# TopLevel.net
KiCad netlist of a schematic drawn in Altium Designer
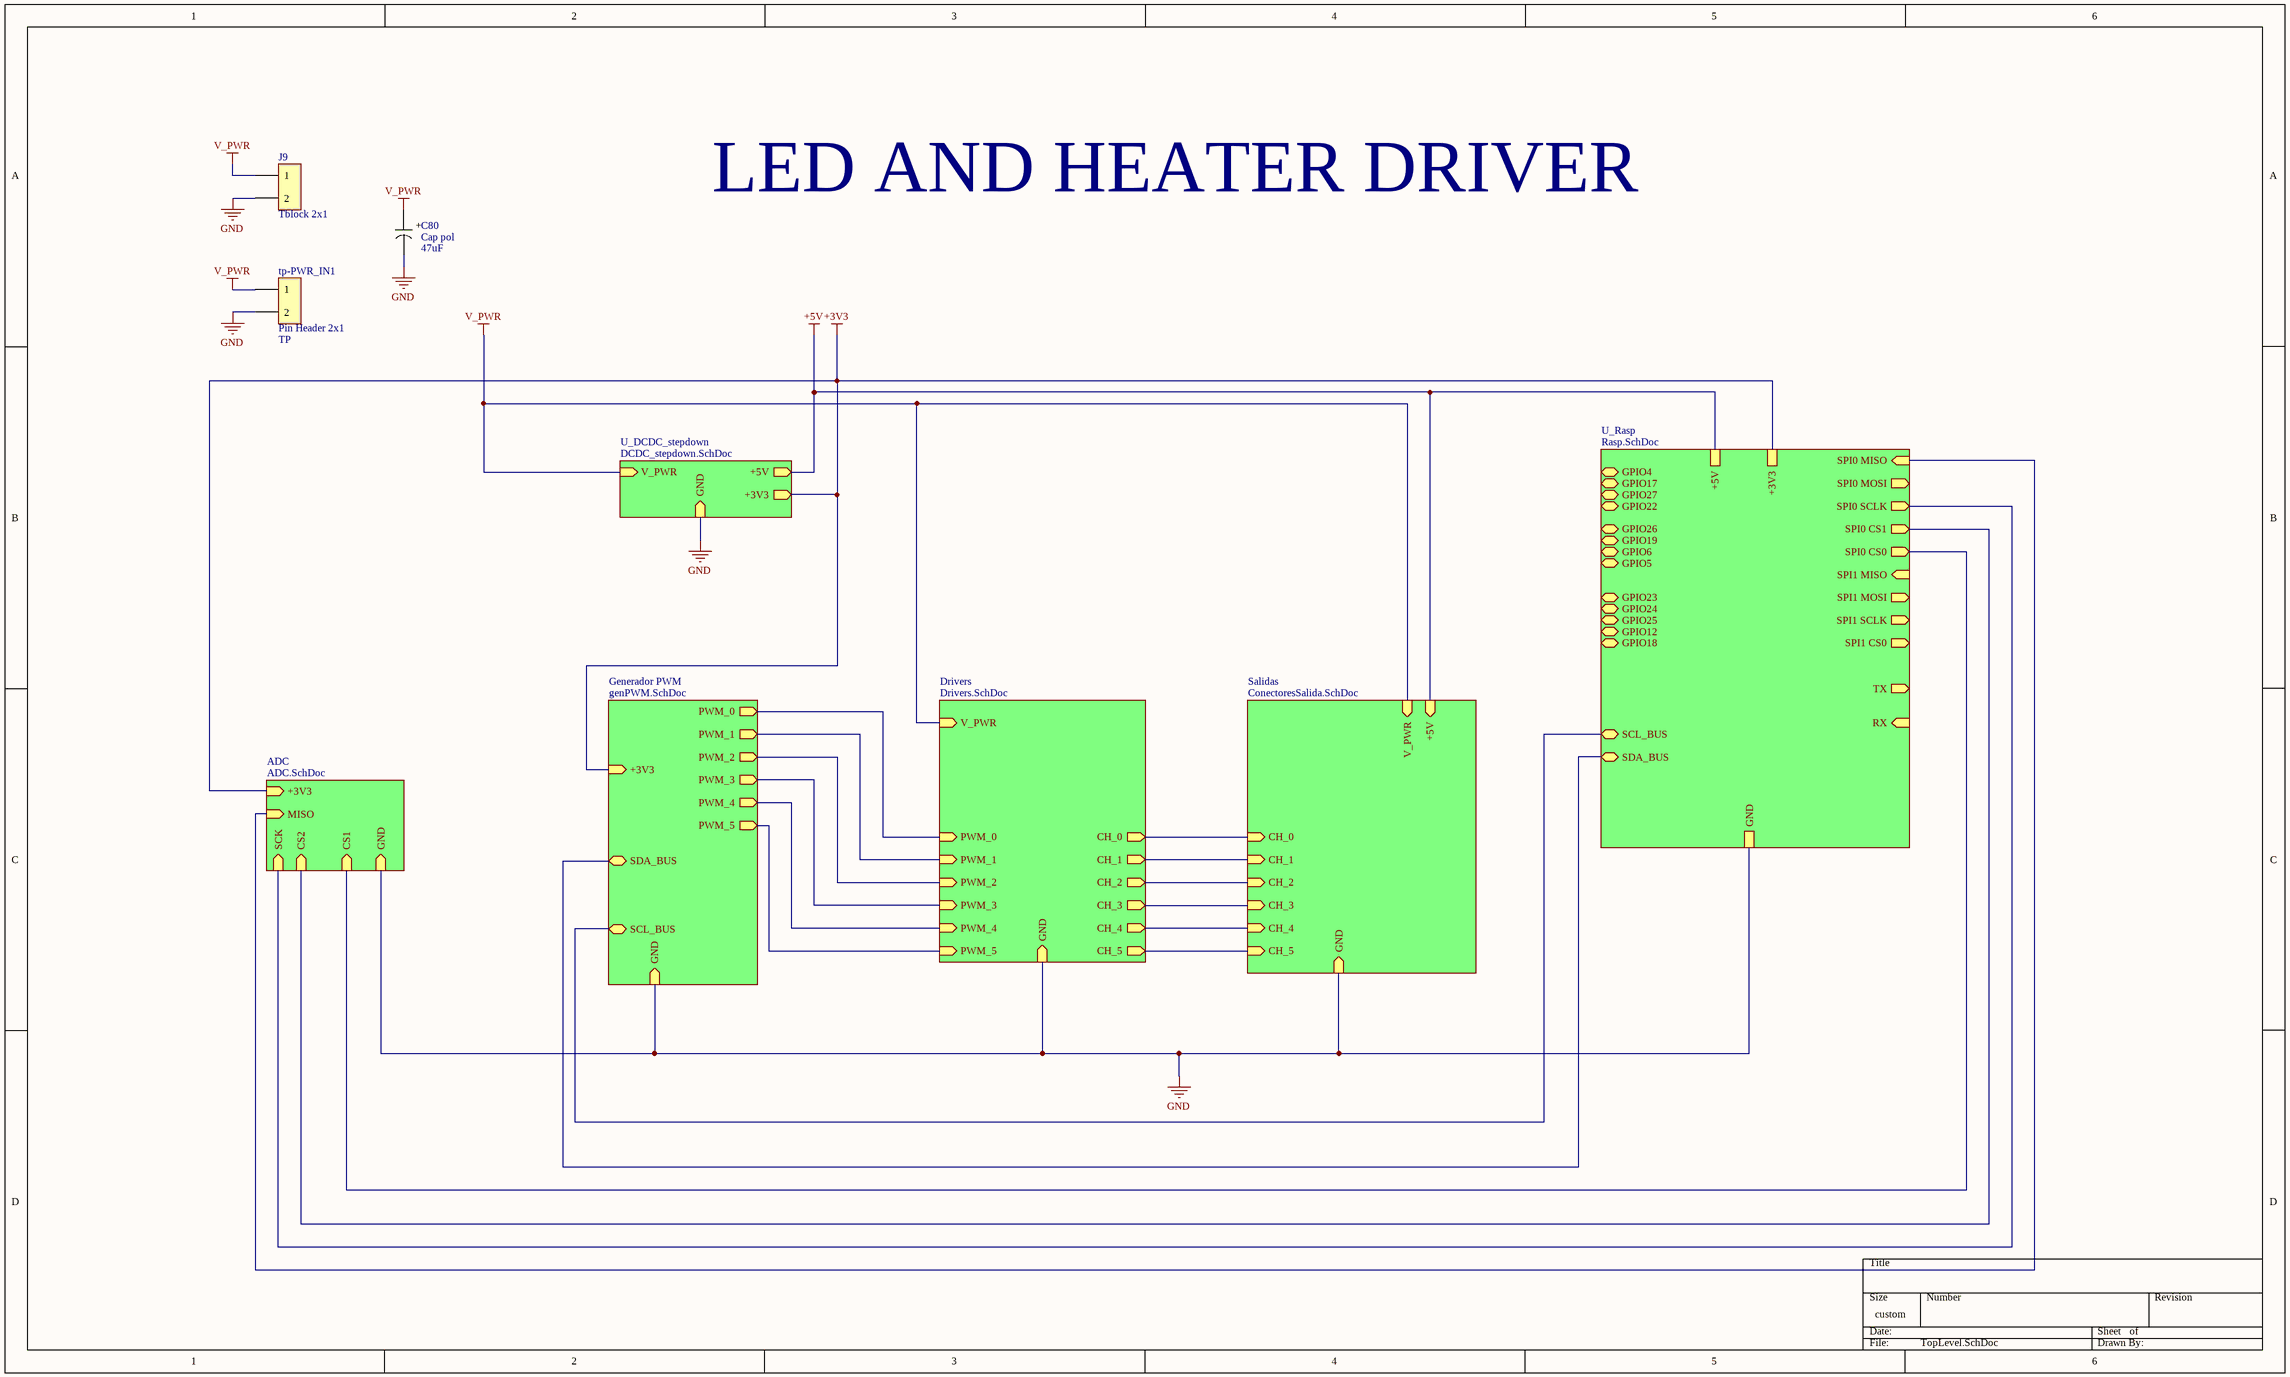
[diagram p0: TopLevel.SchDoc]

(export (version "E")
  (design (tool "Eeschema 10.0.6"))
  (components
    (comp (ref "C80")
      (value "Cap pol")
      (footprint "CAP_SMD_Electrolytic_5X5.4")
      (description "Electrolytic Aluminium Capacitor")
      (fields (field (name "ALTIUM_VALUE") "47uF"))
      (libsource (lib "IoWLabs") (part "Cap pol"))
    )
    (comp (ref "J9")
      (value "Tblock 2x1")
      (footprint "T_BLOCK_2P")
      (description "Screw terminal 2pos, 1 row, 5pitch")
      (fields
        (field (name "MANUFACTURER") "CJT(Changjiang Connectors)")
        (field (name "MANUFACTURER PART NUMBER") "A2547WV-2P")
      )
      (libsource (lib "IoWLabsConnectors") (part "Header - 2x1b"))
    )
    (comp (ref "tp-PWR_IN1")
      (value "Pin Header 2x1")
      (footprint "HDR-TH_P2.54-H-M_A2541WV-2P")
      (description "Pin Header 2pos, 1 row, 2.54 pitch")
      (fields
        (field (name "MANUFACTURER") "CJT(Changjiang Connectors)")
        (field (name "MANUFACTURER PART NUMBER") "A2541WV-2P")
      )
      (libsource (lib "IoWLabsConnectors") (part "Header - 2x1c"))
    )
  )
  (nets
    (net (code "41") (name "GND") (class "Default")
      (node (ref "C80") (pin "1") (pinfunction "1_1") (pintype "passive"))
      (node (ref "J9") (pin "2") (pinfunction "2_2") (pintype "passive"))
      (node (ref "tp-PWR_IN1") (pin "2") (pinfunction "2_2") (pintype "passive"))
    )
    (net (code "42") (name "V_PWR") (class "Default")
      (node (ref "C80") (pin "2") (pinfunction "2_2") (pintype "passive"))
      (node (ref "J9") (pin "1") (pinfunction "1_1") (pintype "passive"))
      (node (ref "tp-PWR_IN1") (pin "1") (pinfunction "1_1") (pintype "passive"))
    )
  )
)
